# Clocks.net
KiCad netlist of a schematic drawn in Altium Designer
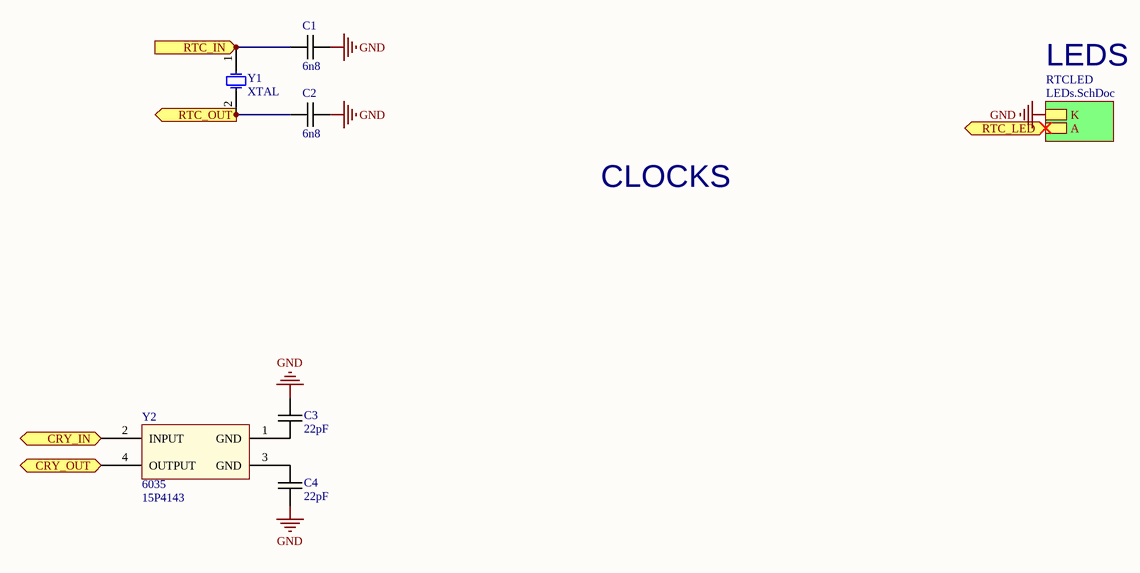
[diagram p0: Clocks.SchDoc]

(export (version "E")
  (design (tool "Eeschema 10.0.6"))
  (components
    (comp (ref "C1")
      (value "6n8")
      (footprint "0603C-GENERIC")
      (description "CAPACITOR 0603 CERAMIC")
      (fields
        (field (name "MANUFACTURER") "Murata Electronics North America")
        (field (name "MANUFACTURER PART NUMBER") "GRM188R71H682KA01D")
      )
      (libsource (lib "RVA_Altium_Library") (part "0603C-6N850V-X7R-MUR"))
    )
    (comp (ref "C2")
      (value "6n8")
      (footprint "0603C-GENERIC")
      (description "CAPACITOR 0603 CERAMIC")
      (fields
        (field (name "MANUFACTURER") "Murata Electronics North America")
        (field (name "MANUFACTURER PART NUMBER") "GRM188R71H682KA01D")
      )
      (libsource (lib "RVA_Altium_Library") (part "0603C-6N850V-X7R-MUR"))
    )
    (comp (ref "C3")
      (value "22pF")
      (footprint "0603C-GENERIC")
      (description "CAPACITOR 0603 CERAMIC")
      (fields (field (name "TOLERANCE") "±5%") (field (name "MANUFACTURER PART NUMBER") "ECJ-1VC1H220J"))
      (libsource (lib "RVA_Altium_Library") (part "0603C-22PF-50V-C0G-PAN"))
    )
    (comp (ref "C4")
      (value "22pF")
      (footprint "0603C-GENERIC")
      (description "CAPACITOR 0603 CERAMIC")
      (fields (field (name "TOLERANCE") "±5%") (field (name "MANUFACTURER PART NUMBER") "ECJ-1VC1H220J"))
      (libsource (lib "RVA_Altium_Library") (part "0603C-22PF-50V-C0G-PAN"))
    )
    (comp (ref "Y1")
      (value "XTAL")
      (footprint "R38")
      (description "Crystal Oscillator")
      (fields (field (name "PUBLISHER") "Altium Limited"))
      (libsource (lib "Miscellaneous Devices") (part "XTAL"))
    )
    (comp (ref "Y2")
      (value "6035")
      (footprint "XTAL 6035")
      (fields (field (name "SUPPLIER PART NUMBER 1") "15P4143"))
      (libsource (lib "RVA_Altium_Library") (part "6035 Quartz"))
    )
  )
  (nets
    (net (code "1") (name "/CRY_IN") (class "Default")
      (node (ref "Y2") (pin "2") (pinfunction "INPUT_2") (pintype "passive"))
    )
    (net (code "2") (name "/CRY_OUT") (class "Default")
      (node (ref "Y2") (pin "4") (pinfunction "OUTPUT_4") (pintype "passive"))
    )
    (net (code "3") (name "/RTC_IN") (class "Default")
      (node (ref "C1") (pin "2") (pintype "passive"))
      (node (ref "Y1") (pin "1") (pinfunction "OSC1_1") (pintype "passive"))
    )
    (net (code "5") (name "/RTC_OUT") (class "Default")
      (node (ref "C2") (pin "2") (pintype "passive"))
      (node (ref "Y1") (pin "2") (pinfunction "OSC2_2") (pintype "passive"))
    )
    (net (code "6") (name "GND") (class "Default")
      (node (ref "C1") (pin "1") (pintype "passive"))
      (node (ref "C2") (pin "1") (pintype "passive"))
      (node (ref "C3") (pin "1") (pintype "passive"))
      (node (ref "C4") (pin "2") (pintype "passive"))
    )
    (net (code "7") (name "Net-(C3-Pad2)") (class "Default")
      (node (ref "C3") (pin "2") (pintype "passive"))
      (node (ref "Y2") (pin "1") (pinfunction "GND_1") (pintype "passive"))
    )
    (net (code "8") (name "Net-(C4-Pad1)") (class "Default")
      (node (ref "C4") (pin "1") (pintype "passive"))
      (node (ref "Y2") (pin "3") (pinfunction "GND_3") (pintype "passive"))
    )
  )
)
